# midi-switcher-smt.net
KiCad netlist of a schematic drawn in EAGLE
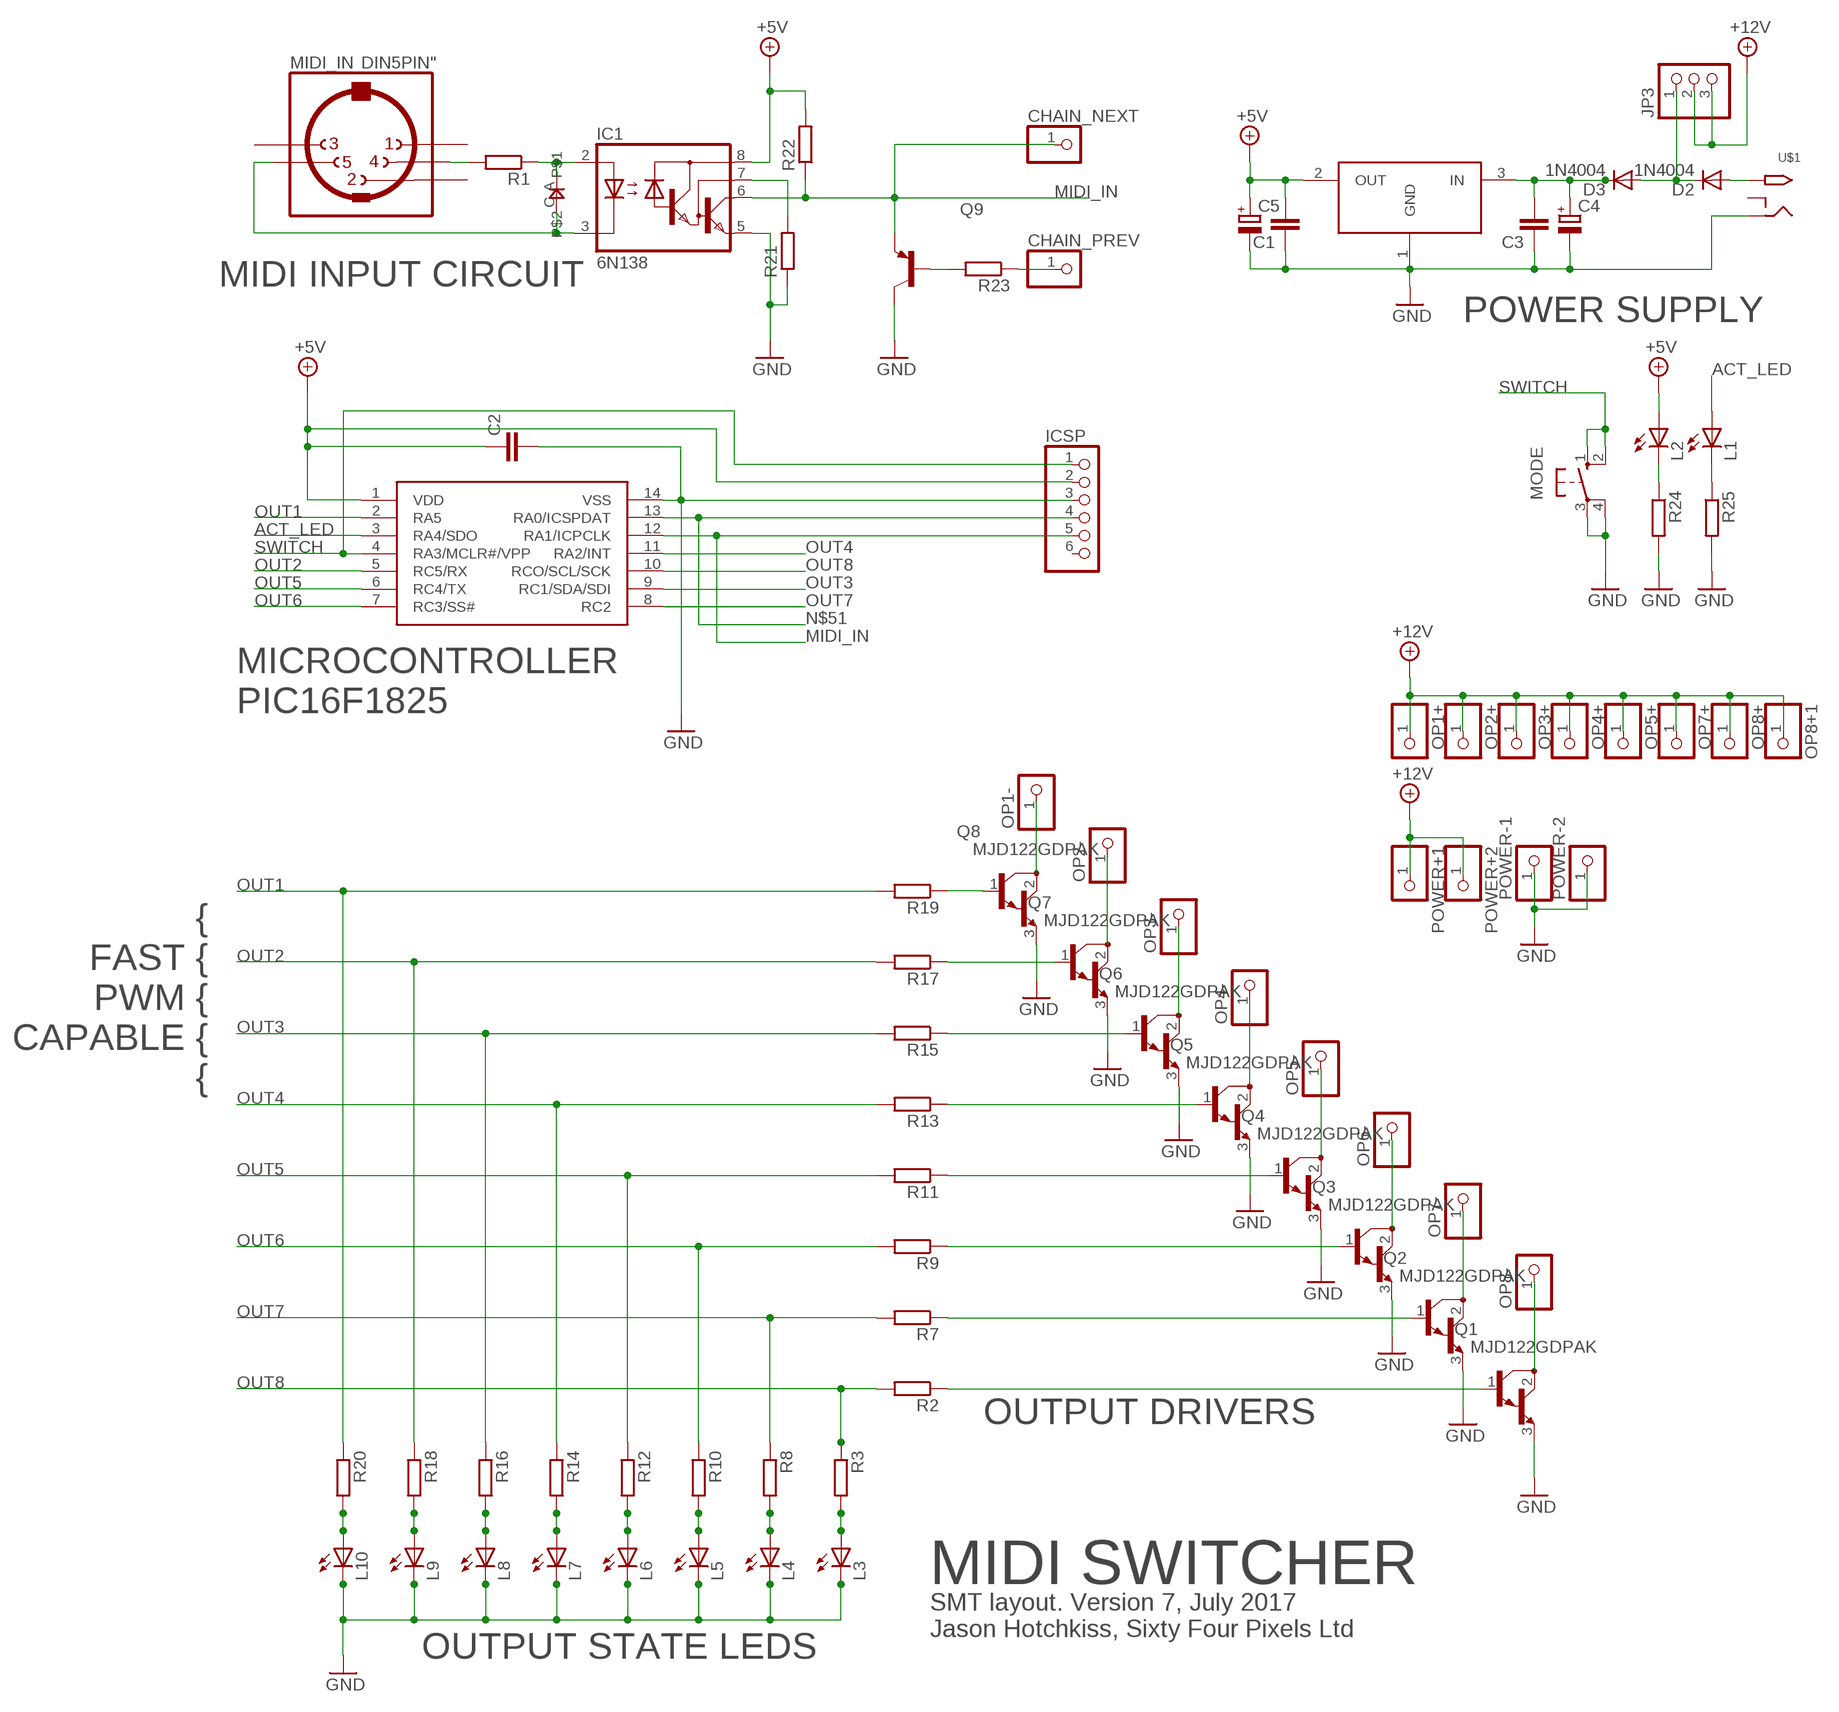
[diagram p0: schematic, sheet 1]

(export (version "E")
  (design (tool "Eeschema 10.0.6"))
  (components
    (comp (ref "C1")
      (value "C-EUC0805")
      (footprint "eagle-import:C0805")
      (libsource (lib "eagle-import") (part "C-EUC0805"))
    )
    (comp (ref "C2")
      (value "C-EUC0805")
      (footprint "eagle-import:C0805")
      (libsource (lib "eagle-import") (part "C-EUC0805"))
    )
    (comp (ref "C3")
      (value "C-EUC0805")
      (footprint "eagle-import:C0805")
      (libsource (lib "eagle-import") (part "C-EUC0805"))
    )
    (comp (ref "C4")
      (value "CPOL-EUE2.5-7")
      (footprint "eagle-import:E2,5-7")
      (libsource (lib "eagle-import") (part "CPOL-EUE2.5-7"))
    )
    (comp (ref "C5")
      (value "CPOL-EUE2.5-6")
      (footprint "eagle-import:E2,5-6")
      (libsource (lib "eagle-import") (part "CPOL-EUE2.5-6"))
    )
    (comp (ref "CHAIN_NEXT")
      (value "PINHD-1X1")
      (footprint "eagle-import:1X01")
      (libsource (lib "eagle-import") (part "PINHD-1X1"))
    )
    (comp (ref "CHAIN_PREV")
      (value "PINHD-1X1")
      (footprint "eagle-import:1X01")
      (libsource (lib "eagle-import") (part "PINHD-1X1"))
    )
    (comp (ref "D1")
      (value "0805DIODE")
      (footprint "eagle-import:0805DIODE")
      (libsource (lib "eagle-import") (part "0805DIODE"))
    )
    (comp (ref "D2")
      (value "1N4004")
      (footprint "eagle-import:DO-VERT")
      (libsource (lib "eagle-import") (part "1N4004"))
    )
    (comp (ref "D3")
      (value "1N4004")
      (footprint "eagle-import:DO-VERT")
      (libsource (lib "eagle-import") (part "1N4004"))
    )
    (comp (ref "IC1")
      (value "6N138")
      (footprint "eagle-import:DIL08")
      (libsource (lib "eagle-import") (part "6N138"))
    )
    (comp (ref "IC2")
      (value "PIC16F1825SO14")
      (footprint "eagle-import:SO14")
      (libsource (lib "eagle-import") (part "PIC16F1825SO14"))
    )
    (comp (ref "IC3")
      (value "LD1086")
      (footprint "eagle-import:DPACK")
      (libsource (lib "eagle-import") (part "LD1086"))
    )
    (comp (ref "ICSP")
      (value "HEADER-1X6")
      (footprint "eagle-import:1X06_OVAL")
      (libsource (lib "eagle-import") (part "HEADER-1X6"))
    )
    (comp (ref "JP3")
      (value "PINHD-1X3")
      (footprint "eagle-import:1X03")
      (libsource (lib "eagle-import") (part "PINHD-1X3"))
    )
    (comp (ref "L1")
      (value "LEDCHIP-LED0805")
      (footprint "eagle-import:CHIP-LED0805")
      (libsource (lib "eagle-import") (part "LEDCHIP-LED0805"))
    )
    (comp (ref "L2")
      (value "LEDCHIP-LED0805")
      (footprint "eagle-import:CHIP-LED0805")
      (libsource (lib "eagle-import") (part "LEDCHIP-LED0805"))
    )
    (comp (ref "L3")
      (value "LEDCHIP-LED0805")
      (footprint "eagle-import:CHIP-LED0805")
      (libsource (lib "eagle-import") (part "LEDCHIP-LED0805"))
    )
    (comp (ref "L4")
      (value "LEDCHIP-LED0805")
      (footprint "eagle-import:CHIP-LED0805")
      (libsource (lib "eagle-import") (part "LEDCHIP-LED0805"))
    )
    (comp (ref "L5")
      (value "LEDCHIP-LED0805")
      (footprint "eagle-import:CHIP-LED0805")
      (libsource (lib "eagle-import") (part "LEDCHIP-LED0805"))
    )
    (comp (ref "L6")
      (value "LEDCHIP-LED0805")
      (footprint "eagle-import:CHIP-LED0805")
      (libsource (lib "eagle-import") (part "LEDCHIP-LED0805"))
    )
    (comp (ref "L7")
      (value "LEDCHIP-LED0805")
      (footprint "eagle-import:CHIP-LED0805")
      (libsource (lib "eagle-import") (part "LEDCHIP-LED0805"))
    )
    (comp (ref "L8")
      (value "LEDCHIP-LED0805")
      (footprint "eagle-import:CHIP-LED0805")
      (libsource (lib "eagle-import") (part "LEDCHIP-LED0805"))
    )
    (comp (ref "L9")
      (value "LEDCHIP-LED0805")
      (footprint "eagle-import:CHIP-LED0805")
      (libsource (lib "eagle-import") (part "LEDCHIP-LED0805"))
    )
    (comp (ref "L10")
      (value "LEDCHIP-LED0805")
      (footprint "eagle-import:CHIP-LED0805")
      (libsource (lib "eagle-import") (part "LEDCHIP-LED0805"))
    )
    (comp (ref "MIDI_IN")
      (value "DIN5PIN\"")
      (footprint "eagle-import:TRUCONN90")
      (libsource (lib "eagle-import") (part "DIN5PIN{dblquote}"))
    )
    (comp (ref "MODE")
      (value "10-XX")
      (footprint "eagle-import:B3F-10XX")
      (libsource (lib "eagle-import") (part "10-XX"))
    )
    (comp (ref "OP1+")
      (value "PINHD-1X1")
      (footprint "eagle-import:1X01")
      (libsource (lib "eagle-import") (part "PINHD-1X1"))
    )
    (comp (ref "OP1-")
      (value "PINHD-1X1")
      (footprint "eagle-import:1X01")
      (libsource (lib "eagle-import") (part "PINHD-1X1"))
    )
    (comp (ref "OP2+")
      (value "PINHD-1X1")
      (footprint "eagle-import:1X01")
      (libsource (lib "eagle-import") (part "PINHD-1X1"))
    )
    (comp (ref "OP2-")
      (value "PINHD-1X1")
      (footprint "eagle-import:1X01")
      (libsource (lib "eagle-import") (part "PINHD-1X1"))
    )
    (comp (ref "OP3+")
      (value "PINHD-1X1")
      (footprint "eagle-import:1X01")
      (libsource (lib "eagle-import") (part "PINHD-1X1"))
    )
    (comp (ref "OP3-")
      (value "PINHD-1X1")
      (footprint "eagle-import:1X01")
      (libsource (lib "eagle-import") (part "PINHD-1X1"))
    )
    (comp (ref "OP4+")
      (value "PINHD-1X1")
      (footprint "eagle-import:1X01")
      (libsource (lib "eagle-import") (part "PINHD-1X1"))
    )
    (comp (ref "OP4-")
      (value "PINHD-1X1")
      (footprint "eagle-import:1X01")
      (libsource (lib "eagle-import") (part "PINHD-1X1"))
    )
    (comp (ref "OP5+")
      (value "PINHD-1X1")
      (footprint "eagle-import:1X01")
      (libsource (lib "eagle-import") (part "PINHD-1X1"))
    )
    (comp (ref "OP5-")
      (value "PINHD-1X1")
      (footprint "eagle-import:1X01")
      (libsource (lib "eagle-import") (part "PINHD-1X1"))
    )
    (comp (ref "OP6-")
      (value "PINHD-1X1")
      (footprint "eagle-import:1X01")
      (libsource (lib "eagle-import") (part "PINHD-1X1"))
    )
    (comp (ref "OP7+")
      (value "PINHD-1X1")
      (footprint "eagle-import:1X01")
      (libsource (lib "eagle-import") (part "PINHD-1X1"))
    )
    (comp (ref "OP7-")
      (value "PINHD-1X1")
      (footprint "eagle-import:1X01")
      (libsource (lib "eagle-import") (part "PINHD-1X1"))
    )
    (comp (ref "OP8+")
      (value "PINHD-1X1")
      (footprint "eagle-import:1X01")
      (libsource (lib "eagle-import") (part "PINHD-1X1"))
    )
    (comp (ref "OP8+1")
      (value "PINHD-1X1")
      (footprint "eagle-import:1X01")
      (libsource (lib "eagle-import") (part "PINHD-1X1"))
    )
    (comp (ref "OP8-")
      (value "PINHD-1X1")
      (footprint "eagle-import:1X01")
      (libsource (lib "eagle-import") (part "PINHD-1X1"))
    )
    (comp (ref "POWER+1")
      (value "PINHD-1X1")
      (footprint "eagle-import:1X01")
      (libsource (lib "eagle-import") (part "PINHD-1X1"))
    )
    (comp (ref "POWER+2")
      (value "PINHD-1X1")
      (footprint "eagle-import:1X01")
      (libsource (lib "eagle-import") (part "PINHD-1X1"))
    )
    (comp (ref "POWER-1")
      (value "PINHD-1X1")
      (footprint "eagle-import:1X01")
      (libsource (lib "eagle-import") (part "PINHD-1X1"))
    )
    (comp (ref "POWER-2")
      (value "PINHD-1X1")
      (footprint "eagle-import:1X01")
      (libsource (lib "eagle-import") (part "PINHD-1X1"))
    )
    (comp (ref "Q1")
      (value "MJD122GDPAK")
      (footprint "eagle-import:DPACK")
      (libsource (lib "eagle-import") (part "MJD122GDPAK"))
    )
    (comp (ref "Q2")
      (value "MJD122GDPAK")
      (footprint "eagle-import:DPACK")
      (libsource (lib "eagle-import") (part "MJD122GDPAK"))
    )
    (comp (ref "Q3")
      (value "MJD122GDPAK")
      (footprint "eagle-import:DPACK")
      (libsource (lib "eagle-import") (part "MJD122GDPAK"))
    )
    (comp (ref "Q4")
      (value "MJD122GDPAK")
      (footprint "eagle-import:DPACK")
      (libsource (lib "eagle-import") (part "MJD122GDPAK"))
    )
    (comp (ref "Q5")
      (value "MJD122GDPAK")
      (footprint "eagle-import:DPACK")
      (libsource (lib "eagle-import") (part "MJD122GDPAK"))
    )
    (comp (ref "Q6")
      (value "MJD122GDPAK")
      (footprint "eagle-import:DPACK")
      (libsource (lib "eagle-import") (part "MJD122GDPAK"))
    )
    (comp (ref "Q7")
      (value "MJD122GDPAK")
      (footprint "eagle-import:DPACK")
      (libsource (lib "eagle-import") (part "MJD122GDPAK"))
    )
    (comp (ref "Q8")
      (value "MJD122GDPAK")
      (footprint "eagle-import:DPACK")
      (libsource (lib "eagle-import") (part "MJD122GDPAK"))
    )
    (comp (ref "Q9")
      (value "MMBT3906LT1-PNP-SOT23-BEC")
      (footprint "eagle-import:SOT23-BEC")
      (libsource (lib "eagle-import") (part "-PNP-SOT23-BECMMBT3906LT1"))
    )
    (comp (ref "R1")
      (value "R-EU_R0805")
      (footprint "eagle-import:R0805")
      (libsource (lib "eagle-import") (part "R-EU_R0805"))
    )
    (comp (ref "R2")
      (value "R-EU_R0805")
      (footprint "eagle-import:R0805")
      (libsource (lib "eagle-import") (part "R-EU_R0805"))
    )
    (comp (ref "R3")
      (value "R-EU_R0805")
      (footprint "eagle-import:R0805")
      (libsource (lib "eagle-import") (part "R-EU_R0805"))
    )
    (comp (ref "R7")
      (value "R-EU_R0805")
      (footprint "eagle-import:R0805")
      (libsource (lib "eagle-import") (part "R-EU_R0805"))
    )
    (comp (ref "R8")
      (value "R-EU_R0805")
      (footprint "eagle-import:R0805")
      (libsource (lib "eagle-import") (part "R-EU_R0805"))
    )
    (comp (ref "R9")
      (value "R-EU_R0805")
      (footprint "eagle-import:R0805")
      (libsource (lib "eagle-import") (part "R-EU_R0805"))
    )
    (comp (ref "R10")
      (value "R-EU_R0805")
      (footprint "eagle-import:R0805")
      (libsource (lib "eagle-import") (part "R-EU_R0805"))
    )
    (comp (ref "R11")
      (value "R-EU_R0805")
      (footprint "eagle-import:R0805")
      (libsource (lib "eagle-import") (part "R-EU_R0805"))
    )
    (comp (ref "R12")
      (value "R-EU_R0805")
      (footprint "eagle-import:R0805")
      (libsource (lib "eagle-import") (part "R-EU_R0805"))
    )
    (comp (ref "R13")
      (value "R-EU_R0805")
      (footprint "eagle-import:R0805")
      (libsource (lib "eagle-import") (part "R-EU_R0805"))
    )
    (comp (ref "R14")
      (value "R-EU_R0805")
      (footprint "eagle-import:R0805")
      (libsource (lib "eagle-import") (part "R-EU_R0805"))
    )
    (comp (ref "R15")
      (value "R-EU_R0805")
      (footprint "eagle-import:R0805")
      (libsource (lib "eagle-import") (part "R-EU_R0805"))
    )
    (comp (ref "R16")
      (value "R-EU_R0805")
      (footprint "eagle-import:R0805")
      (libsource (lib "eagle-import") (part "R-EU_R0805"))
    )
    (comp (ref "R17")
      (value "R-EU_R0805")
      (footprint "eagle-import:R0805")
      (libsource (lib "eagle-import") (part "R-EU_R0805"))
    )
    (comp (ref "R18")
      (value "R-EU_R0805")
      (footprint "eagle-import:R0805")
      (libsource (lib "eagle-import") (part "R-EU_R0805"))
    )
    (comp (ref "R19")
      (value "R-EU_R0805")
      (footprint "eagle-import:R0805")
      (libsource (lib "eagle-import") (part "R-EU_R0805"))
    )
    (comp (ref "R20")
      (value "R-EU_R0805")
      (footprint "eagle-import:R0805")
      (libsource (lib "eagle-import") (part "R-EU_R0805"))
    )
    (comp (ref "R21")
      (value "R-EU_R0805")
      (footprint "eagle-import:R0805")
      (libsource (lib "eagle-import") (part "R-EU_R0805"))
    )
    (comp (ref "R22")
      (value "R-EU_R0805")
      (footprint "eagle-import:R0805")
      (libsource (lib "eagle-import") (part "R-EU_R0805"))
    )
    (comp (ref "R23")
      (value "R-EU_R0805")
      (footprint "eagle-import:R0805")
      (libsource (lib "eagle-import") (part "R-EU_R0805"))
    )
    (comp (ref "R24")
      (value "R-EU_R0805")
      (footprint "eagle-import:R0805")
      (libsource (lib "eagle-import") (part "R-EU_R0805"))
    )
    (comp (ref "R25")
      (value "R-EU_R0805")
      (footprint "eagle-import:R0805")
      (libsource (lib "eagle-import") (part "R-EU_R0805"))
    )
    (comp (ref "U$1")
      (value "2.1MMJACKTHM")
      (footprint "eagle-import:PJ-102A")
      (libsource (lib "eagle-import") (part "2.1MMJACKTHM"))
    )
  )
  (nets
    (net (code "1") (name "+5V") (class "Default")
      (node (ref "C1") (pin "2") (pinfunction "2_2") (pintype "passive"))
      (node (ref "C2") (pin "1") (pinfunction "1_1") (pintype "passive"))
      (node (ref "C5") (pin "+") (pinfunction "+_+") (pintype "passive"))
      (node (ref "IC1") (pin "8") (pinfunction "VCC_8") (pintype "passive"))
      (node (ref "IC2") (pin "1") (pinfunction "VDD_1") (pintype "power_in"))
      (node (ref "IC3") (pin "2") (pinfunction "OUT_2") (pintype "bidirectional"))
      (node (ref "ICSP") (pin "2") (pinfunction "2_2") (pintype "passive"))
      (node (ref "L2") (pin "A") (pinfunction "A_A") (pintype "passive"))
      (node (ref "R22") (pin "2") (pinfunction "2_2") (pintype "passive"))
    )
    (net (code "2") (name "+12V") (class "Default")
      (node (ref "JP3") (pin "2") (pinfunction "2_2") (pintype "passive"))
      (node (ref "JP3") (pin "3") (pinfunction "3_3") (pintype "passive"))
      (node (ref "OP1+") (pin "1") (pinfunction "1_1") (pintype "passive"))
      (node (ref "OP2+") (pin "1") (pinfunction "1_1") (pintype "passive"))
      (node (ref "OP3+") (pin "1") (pinfunction "1_1") (pintype "passive"))
      (node (ref "OP4+") (pin "1") (pinfunction "1_1") (pintype "passive"))
      (node (ref "OP5+") (pin "1") (pinfunction "1_1") (pintype "passive"))
      (node (ref "OP7+") (pin "1") (pinfunction "1_1") (pintype "passive"))
      (node (ref "OP8+") (pin "1") (pinfunction "1_1") (pintype "passive"))
      (node (ref "OP8+1") (pin "1") (pinfunction "1_1") (pintype "passive"))
      (node (ref "POWER+1") (pin "1") (pinfunction "1_1") (pintype "passive"))
      (node (ref "POWER+2") (pin "1") (pinfunction "1_1") (pintype "passive"))
    )
    (net (code "3") (name "/ACT_LED") (class "Default")
      (node (ref "IC2") (pin "3") (pinfunction "RA4/SDO_3") (pintype "bidirectional"))
      (node (ref "L1") (pin "A") (pinfunction "A_A") (pintype "passive"))
    )
    (net (code "4") (name "/MIDI_IN") (class "Default")
      (node (ref "CHAIN_NEXT") (pin "1") (pinfunction "1_1") (pintype "passive"))
      (node (ref "IC1") (pin "6") (pinfunction "VO_6") (pintype "passive"))
      (node (ref "IC2") (pin "12") (pinfunction "RA1/ICPCLK_12") (pintype "bidirectional"))
      (node (ref "ICSP") (pin "5") (pinfunction "5_5") (pintype "passive"))
      (node (ref "Q9") (pin "E") (pinfunction "E_E") (pintype "passive"))
      (node (ref "R22") (pin "1") (pinfunction "1_1") (pintype "passive"))
    )
    (net (code "5") (name "/N$51") (class "Default")
      (node (ref "IC2") (pin "13") (pinfunction "RA0/ICSPDAT_13") (pintype "bidirectional"))
      (node (ref "ICSP") (pin "4") (pinfunction "4_4") (pintype "passive"))
    )
    (net (code "6") (name "/OUT1") (class "Default")
      (node (ref "IC2") (pin "2") (pinfunction "RA5_2") (pintype "bidirectional"))
      (node (ref "R19") (pin "2") (pinfunction "2_2") (pintype "passive"))
      (node (ref "R20") (pin "1") (pinfunction "1_1") (pintype "passive"))
    )
    (net (code "7") (name "/OUT2") (class "Default")
      (node (ref "IC2") (pin "5") (pinfunction "RC5/RX_5") (pintype "bidirectional"))
      (node (ref "R17") (pin "2") (pinfunction "2_2") (pintype "passive"))
      (node (ref "R18") (pin "1") (pinfunction "1_1") (pintype "passive"))
    )
    (net (code "8") (name "/OUT3") (class "Default")
      (node (ref "IC2") (pin "9") (pinfunction "RC1/SDA/SDI_9") (pintype "bidirectional"))
      (node (ref "R15") (pin "2") (pinfunction "2_2") (pintype "passive"))
      (node (ref "R16") (pin "1") (pinfunction "1_1") (pintype "passive"))
    )
    (net (code "9") (name "/OUT4") (class "Default")
      (node (ref "IC2") (pin "11") (pinfunction "RA2/INT_11") (pintype "bidirectional"))
      (node (ref "R13") (pin "2") (pinfunction "2_2") (pintype "passive"))
      (node (ref "R14") (pin "1") (pinfunction "1_1") (pintype "passive"))
    )
    (net (code "10") (name "/OUT5") (class "Default")
      (node (ref "IC2") (pin "6") (pinfunction "RC4/TX_6") (pintype "bidirectional"))
      (node (ref "R11") (pin "2") (pinfunction "2_2") (pintype "passive"))
      (node (ref "R12") (pin "1") (pinfunction "1_1") (pintype "passive"))
    )
    (net (code "11") (name "/OUT6") (class "Default")
      (node (ref "IC2") (pin "7") (pinfunction "RC3/SS#_7") (pintype "bidirectional"))
      (node (ref "R10") (pin "1") (pinfunction "1_1") (pintype "passive"))
      (node (ref "R9") (pin "2") (pinfunction "2_2") (pintype "passive"))
    )
    (net (code "12") (name "/OUT7") (class "Default")
      (node (ref "IC2") (pin "8") (pinfunction "RC2_8") (pintype "bidirectional"))
      (node (ref "R7") (pin "2") (pinfunction "2_2") (pintype "passive"))
      (node (ref "R8") (pin "1") (pinfunction "1_1") (pintype "passive"))
    )
    (net (code "13") (name "/OUT8") (class "Default")
      (node (ref "IC2") (pin "10") (pinfunction "RCO/SCL/SCK_10") (pintype "bidirectional"))
      (node (ref "R2") (pin "2") (pinfunction "2_2") (pintype "passive"))
      (node (ref "R3") (pin "1") (pinfunction "1_1") (pintype "passive"))
    )
    (net (code "14") (name "/SWITCH") (class "Default")
      (node (ref "IC2") (pin "4") (pinfunction "RA3/MCLR#/VPP_4") (pintype "input"))
      (node (ref "ICSP") (pin "1") (pinfunction "1_1") (pintype "passive"))
      (node (ref "MODE") (pin "1") (pinfunction "S_1") (pintype "passive"))
      (node (ref "MODE") (pin "2") (pinfunction "S1_2") (pintype "passive"))
    )
    (net (code "15") (name "GND") (class "Default")
      (node (ref "C1") (pin "1") (pinfunction "1_1") (pintype "passive"))
      (node (ref "C2") (pin "2") (pinfunction "2_2") (pintype "passive"))
      (node (ref "C3") (pin "1") (pinfunction "1_1") (pintype "passive"))
      (node (ref "C4") (pin "-") (pinfunction "-_-") (pintype "passive"))
      (node (ref "C5") (pin "-") (pinfunction "-_-") (pintype "passive"))
      (node (ref "IC1") (pin "5") (pinfunction "GND_5") (pintype "passive"))
      (node (ref "IC2") (pin "14") (pinfunction "VSS_14") (pintype "power_in"))
      (node (ref "IC3") (pin "1") (pinfunction "GND_1") (pintype "bidirectional"))
      (node (ref "ICSP") (pin "3") (pinfunction "3_3") (pintype "passive"))
      (node (ref "L10") (pin "C") (pinfunction "C_C") (pintype "passive"))
      (node (ref "L3") (pin "C") (pinfunction "C_C") (pintype "passive"))
      (node (ref "L4") (pin "C") (pinfunction "C_C") (pintype "passive"))
      (node (ref "L5") (pin "C") (pinfunction "C_C") (pintype "passive"))
      (node (ref "L6") (pin "C") (pinfunction "C_C") (pintype "passive"))
      (node (ref "L7") (pin "C") (pinfunction "C_C") (pintype "passive"))
      (node (ref "L8") (pin "C") (pinfunction "C_C") (pintype "passive"))
      (node (ref "L9") (pin "C") (pinfunction "C_C") (pintype "passive"))
      (node (ref "MODE") (pin "3") (pinfunction "P_3") (pintype "passive"))
      (node (ref "MODE") (pin "4") (pinfunction "P1_4") (pintype "passive"))
      (node (ref "POWER-1") (pin "1") (pinfunction "1_1") (pintype "passive"))
      (node (ref "POWER-2") (pin "1") (pinfunction "1_1") (pintype "passive"))
      (node (ref "Q1") (pin "3") (pinfunction "E_3") (pintype "passive"))
      (node (ref "Q2") (pin "3") (pinfunction "E_3") (pintype "passive"))
      (node (ref "Q3") (pin "3") (pinfunction "E_3") (pintype "passive"))
      (node (ref "Q4") (pin "3") (pinfunction "E_3") (pintype "passive"))
      (node (ref "Q5") (pin "3") (pinfunction "E_3") (pintype "passive"))
      (node (ref "Q6") (pin "3") (pinfunction "E_3") (pintype "passive"))
      (node (ref "Q7") (pin "3") (pinfunction "E_3") (pintype "passive"))
      (node (ref "Q8") (pin "3") (pinfunction "E_3") (pintype "passive"))
      (node (ref "Q9") (pin "C") (pinfunction "C_C") (pintype "passive"))
      (node (ref "R21") (pin "1") (pinfunction "1_1") (pintype "passive"))
      (node (ref "R24") (pin "2") (pinfunction "2_2") (pintype "passive"))
      (node (ref "R25") (pin "2") (pinfunction "2_2") (pintype "passive"))
      (node (ref "U$1") (pin "RING") (pinfunction "RING_RING") (pintype "bidirectional"))
    )
    (net (code "16") (name "Net-(CHAIN_PREV-Pad1)") (class "Default")
      (node (ref "CHAIN_PREV") (pin "1") (pinfunction "1_1") (pintype "passive"))
      (node (ref "R23") (pin "1") (pinfunction "1_1") (pintype "passive"))
    )
    (net (code "17") (name "Net-(D1-P$1)") (class "Default")
      (node (ref "D1") (pin "C") (pinfunction "P$1_C") (pintype "bidirectional"))
      (node (ref "IC1") (pin "3") (pinfunction "C_3") (pintype "passive"))
      (node (ref "MIDI_IN") (pin "5") (pinfunction "5_5") (pintype "passive"))
    )
    (net (code "18") (name "Net-(D1-P$2)") (class "Default")
      (node (ref "D1") (pin "A") (pinfunction "P$2_A") (pintype "bidirectional"))
      (node (ref "IC1") (pin "2") (pinfunction "A_2") (pintype "passive"))
      (node (ref "R1") (pin "1") (pinfunction "1_1") (pintype "passive"))
    )
    (net (code "19") (name "Net-(D2-PadA)") (class "Default")
      (node (ref "D2") (pin "A") (pinfunction "A_A") (pintype "passive"))
      (node (ref "U$1") (pin "TIP") (pinfunction "TIP_TIP") (pintype "bidirectional"))
    )
    (net (code "20") (name "Net-(D2-PadC)") (class "Default")
      (node (ref "D2") (pin "C") (pinfunction "C_C") (pintype "passive"))
      (node (ref "D3") (pin "A") (pinfunction "A_A") (pintype "passive"))
      (node (ref "JP3") (pin "1") (pinfunction "1_1") (pintype "passive"))
    )
    (net (code "21") (name "Net-(IC1-VB)") (class "Default")
      (node (ref "IC1") (pin "7") (pinfunction "VB_7") (pintype "passive"))
      (node (ref "R21") (pin "2") (pinfunction "2_2") (pintype "passive"))
    )
    (net (code "22") (name "Net-(IC3-IN)") (class "Default")
      (node (ref "C3") (pin "2") (pinfunction "2_2") (pintype "passive"))
      (node (ref "C4") (pin "+") (pinfunction "+_+") (pintype "passive"))
      (node (ref "D3") (pin "C") (pinfunction "C_C") (pintype "passive"))
      (node (ref "IC3") (pin "3") (pinfunction "IN_3") (pintype "bidirectional"))
    )
    (net (code "23") (name "Net-(L1-PadC)") (class "Default")
      (node (ref "L1") (pin "C") (pinfunction "C_C") (pintype "passive"))
      (node (ref "R25") (pin "1") (pinfunction "1_1") (pintype "passive"))
    )
    (net (code "24") (name "Net-(L2-PadC)") (class "Default")
      (node (ref "L2") (pin "C") (pinfunction "C_C") (pintype "passive"))
      (node (ref "R24") (pin "1") (pinfunction "1_1") (pintype "passive"))
    )
    (net (code "25") (name "Net-(L3-PadA)") (class "Default")
      (node (ref "L3") (pin "A") (pinfunction "A_A") (pintype "passive"))
      (node (ref "R3") (pin "2") (pinfunction "2_2") (pintype "passive"))
    )
    (net (code "26") (name "Net-(L4-PadA)") (class "Default")
      (node (ref "L4") (pin "A") (pinfunction "A_A") (pintype "passive"))
      (node (ref "R8") (pin "2") (pinfunction "2_2") (pintype "passive"))
    )
    (net (code "27") (name "Net-(L5-PadA)") (class "Default")
      (node (ref "L5") (pin "A") (pinfunction "A_A") (pintype "passive"))
      (node (ref "R10") (pin "2") (pinfunction "2_2") (pintype "passive"))
    )
    (net (code "28") (name "Net-(L6-PadA)") (class "Default")
      (node (ref "L6") (pin "A") (pinfunction "A_A") (pintype "passive"))
      (node (ref "R12") (pin "2") (pinfunction "2_2") (pintype "passive"))
    )
    (net (code "29") (name "Net-(L7-PadA)") (class "Default")
      (node (ref "L7") (pin "A") (pinfunction "A_A") (pintype "passive"))
      (node (ref "R14") (pin "2") (pinfunction "2_2") (pintype "passive"))
    )
    (net (code "30") (name "Net-(L8-PadA)") (class "Default")
      (node (ref "L8") (pin "A") (pinfunction "A_A") (pintype "passive"))
      (node (ref "R16") (pin "2") (pinfunction "2_2") (pintype "passive"))
    )
    (net (code "31") (name "Net-(L9-PadA)") (class "Default")
      (node (ref "L9") (pin "A") (pinfunction "A_A") (pintype "passive"))
      (node (ref "R18") (pin "2") (pinfunction "2_2") (pintype "passive"))
    )
    (net (code "32") (name "Net-(L10-PadA)") (class "Default")
      (node (ref "L10") (pin "A") (pinfunction "A_A") (pintype "passive"))
      (node (ref "R20") (pin "2") (pinfunction "2_2") (pintype "passive"))
    )
    (net (code "33") (name "Net-(MIDI_IN-Pad4)") (class "Default")
      (node (ref "MIDI_IN") (pin "4") (pinfunction "4_4") (pintype "passive"))
      (node (ref "R1") (pin "2") (pinfunction "2_2") (pintype "passive"))
    )
    (net (code "34") (name "Net-(Q1-B)") (class "Default")
      (node (ref "Q1") (pin "1") (pinfunction "B_1") (pintype "passive"))
      (node (ref "R2") (pin "1") (pinfunction "1_1") (pintype "passive"))
    )
    (net (code "35") (name "Net-(Q1-C)") (class "Default")
      (node (ref "OP8-") (pin "1") (pinfunction "1_1") (pintype "passive"))
      (node (ref "Q1") (pin "2") (pinfunction "C_2") (pintype "passive"))
    )
    (net (code "36") (name "Net-(Q2-B)") (class "Default")
      (node (ref "Q2") (pin "1") (pinfunction "B_1") (pintype "passive"))
      (node (ref "R7") (pin "1") (pinfunction "1_1") (pintype "passive"))
    )
    (net (code "37") (name "Net-(Q2-C)") (class "Default")
      (node (ref "OP7-") (pin "1") (pinfunction "1_1") (pintype "passive"))
      (node (ref "Q2") (pin "2") (pinfunction "C_2") (pintype "passive"))
    )
    (net (code "38") (name "Net-(Q3-B)") (class "Default")
      (node (ref "Q3") (pin "1") (pinfunction "B_1") (pintype "passive"))
      (node (ref "R9") (pin "1") (pinfunction "1_1") (pintype "passive"))
    )
    (net (code "39") (name "Net-(Q3-C)") (class "Default")
      (node (ref "OP6-") (pin "1") (pinfunction "1_1") (pintype "passive"))
      (node (ref "Q3") (pin "2") (pinfunction "C_2") (pintype "passive"))
    )
    (net (code "40") (name "Net-(Q4-B)") (class "Default")
      (node (ref "Q4") (pin "1") (pinfunction "B_1") (pintype "passive"))
      (node (ref "R11") (pin "1") (pinfunction "1_1") (pintype "passive"))
    )
    (net (code "41") (name "Net-(Q4-C)") (class "Default")
      (node (ref "OP5-") (pin "1") (pinfunction "1_1") (pintype "passive"))
      (node (ref "Q4") (pin "2") (pinfunction "C_2") (pintype "passive"))
    )
    (net (code "42") (name "Net-(Q5-B)") (class "Default")
      (node (ref "Q5") (pin "1") (pinfunction "B_1") (pintype "passive"))
      (node (ref "R13") (pin "1") (pinfunction "1_1") (pintype "passive"))
    )
    (net (code "43") (name "Net-(Q5-C)") (class "Default")
      (node (ref "OP4-") (pin "1") (pinfunction "1_1") (pintype "passive"))
      (node (ref "Q5") (pin "2") (pinfunction "C_2") (pintype "passive"))
    )
    (net (code "44") (name "Net-(Q6-B)") (class "Default")
      (node (ref "Q6") (pin "1") (pinfunction "B_1") (pintype "passive"))
      (node (ref "R15") (pin "1") (pinfunction "1_1") (pintype "passive"))
    )
    (net (code "45") (name "Net-(Q6-C)") (class "Default")
      (node (ref "OP3-") (pin "1") (pinfunction "1_1") (pintype "passive"))
      (node (ref "Q6") (pin "2") (pinfunction "C_2") (pintype "passive"))
    )
    (net (code "46") (name "Net-(Q7-B)") (class "Default")
      (node (ref "Q7") (pin "1") (pinfunction "B_1") (pintype "passive"))
      (node (ref "R17") (pin "1") (pinfunction "1_1") (pintype "passive"))
    )
    (net (code "47") (name "Net-(Q7-C)") (class "Default")
      (node (ref "OP2-") (pin "1") (pinfunction "1_1") (pintype "passive"))
      (node (ref "Q7") (pin "2") (pinfunction "C_2") (pintype "passive"))
    )
    (net (code "48") (name "Net-(Q8-B)") (class "Default")
      (node (ref "Q8") (pin "1") (pinfunction "B_1") (pintype "passive"))
      (node (ref "R19") (pin "1") (pinfunction "1_1") (pintype "passive"))
    )
    (net (code "49") (name "Net-(Q8-C)") (class "Default")
      (node (ref "OP1-") (pin "1") (pinfunction "1_1") (pintype "passive"))
      (node (ref "Q8") (pin "2") (pinfunction "C_2") (pintype "passive"))
    )
    (net (code "50") (name "Net-(Q9-PadB)") (class "Default")
      (node (ref "Q9") (pin "B") (pinfunction "B_B") (pintype "passive"))
      (node (ref "R23") (pin "2") (pinfunction "2_2") (pintype "passive"))
    )
    (net (code "51") (name "unconnected-(ICSP-Pad6)") (class "Default")
      (node (ref "ICSP") (pin "6") (pinfunction "6_6") (pintype "passive"))
    )
    (net (code "52") (name "unconnected-(MIDI_IN-Pad1)") (class "Default")
      (node (ref "MIDI_IN") (pin "1") (pinfunction "1_1") (pintype "passive"))
    )
    (net (code "53") (name "unconnected-(MIDI_IN-Pad2)") (class "Default")
      (node (ref "MIDI_IN") (pin "2") (pinfunction "2_2") (pintype "passive"))
    )
    (net (code "54") (name "unconnected-(MIDI_IN-Pad3)") (class "Default")
      (node (ref "MIDI_IN") (pin "3") (pinfunction "3_3") (pintype "passive"))
    )
    (net (code "55") (name "unconnected-(U$1-PadRING_SW)") (class "Default")
      (node (ref "U$1") (pin "RING_SW") (pinfunction "RING_SW_RING_SW") (pintype "bidirectional"))
    )
  )
)
